# LCD_TFT_40_Pin.net
KiCad netlist of a schematic drawn in Altium Designer
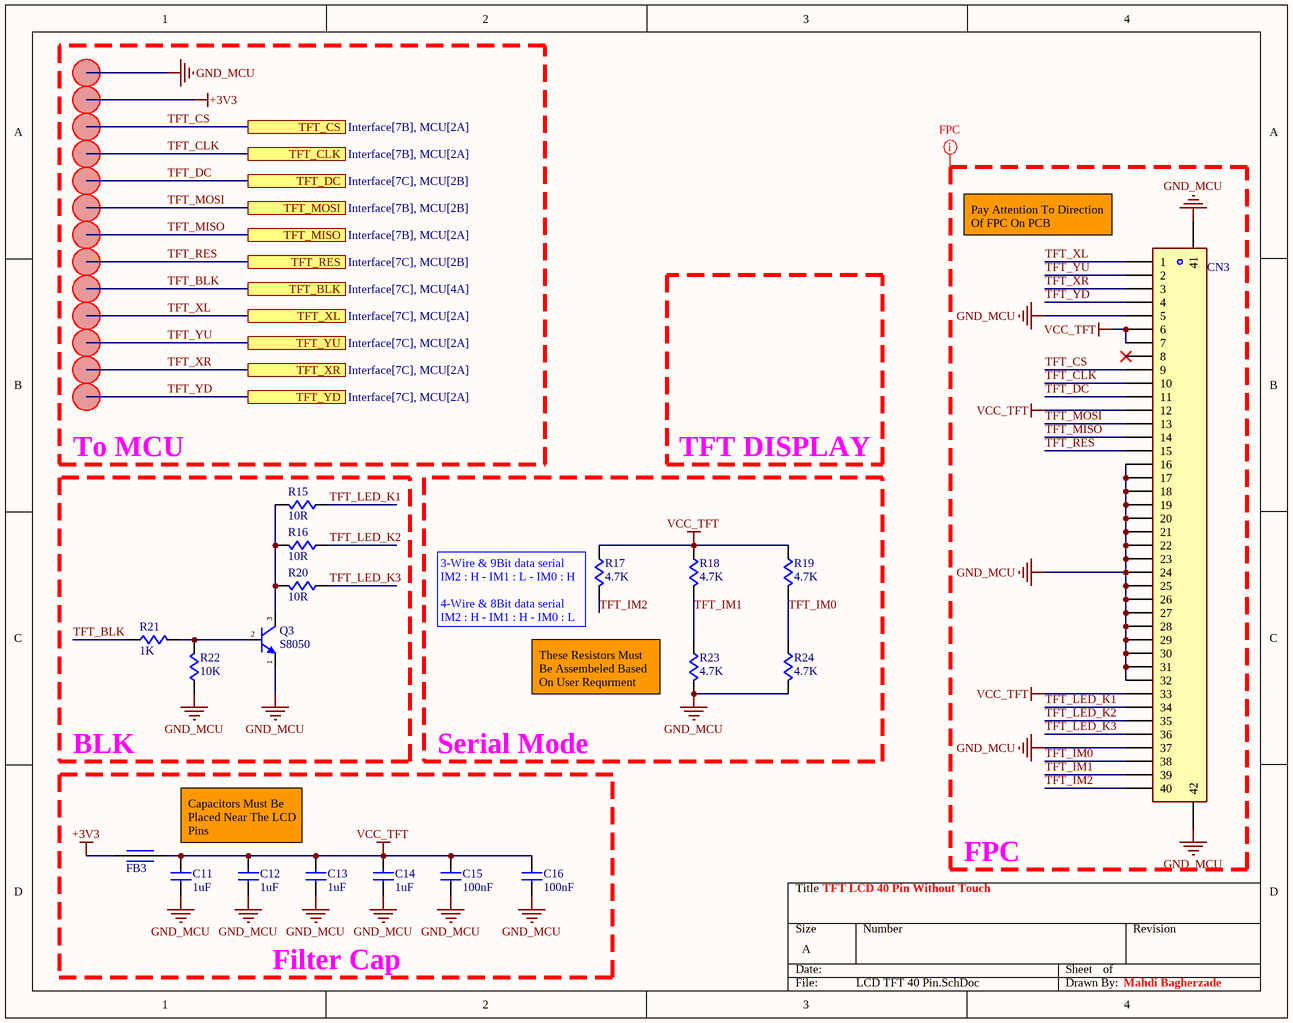
[diagram p0: LCD TFT 40 Pin.SchDoc]

(export (version "E")
  (design (tool "Eeschema 10.0.6"))
  (components
    (comp (ref "C11")
      (value "1uF")
      (footprint "C-0805")
      (description "CAPACITOR")
      (fields
        (field (name "VOLTAGE") "50V")
        (field (name "TOLERANCE") "X7R")
        (field (name "PUBLISHER") "Mahdi Bagherzadeh")
      )
      (libsource (lib "Mahdi-Bagherzadeh") (part "CAP-CER"))
    )
    (comp (ref "C12")
      (value "1uF")
      (footprint "C-0805")
      (description "CAPACITOR")
      (fields
        (field (name "VOLTAGE") "50V")
        (field (name "TOLERANCE") "X7R")
        (field (name "PUBLISHER") "Mahdi Bagherzadeh")
      )
      (libsource (lib "Mahdi-Bagherzadeh") (part "CAP-CER"))
    )
    (comp (ref "C13")
      (value "1uF")
      (footprint "C-0805")
      (description "CAPACITOR")
      (fields
        (field (name "VOLTAGE") "50V")
        (field (name "TOLERANCE") "X7R")
        (field (name "PUBLISHER") "Mahdi Bagherzadeh")
      )
      (libsource (lib "Mahdi-Bagherzadeh") (part "CAP-CER"))
    )
    (comp (ref "C14")
      (value "1uF")
      (footprint "C-0805")
      (description "CAPACITOR")
      (fields
        (field (name "VOLTAGE") "50V")
        (field (name "TOLERANCE") "X7R")
        (field (name "PUBLISHER") "Mahdi Bagherzadeh")
      )
      (libsource (lib "Mahdi-Bagherzadeh") (part "CAP-CER"))
    )
    (comp (ref "C15")
      (value "100nF")
      (footprint "C-0805")
      (description "CAPACITOR")
      (fields
        (field (name "VOLTAGE") "50V")
        (field (name "TOLERANCE") "X7R")
        (field (name "PUBLISHER") "Mahdi Bagherzadeh")
      )
      (libsource (lib "Mahdi-Bagherzadeh") (part "CAP-CER"))
    )
    (comp (ref "C16")
      (value "100nF")
      (footprint "C-0805")
      (description "CAPACITOR")
      (fields
        (field (name "VOLTAGE") "50V")
        (field (name "TOLERANCE") "X7R")
        (field (name "PUBLISHER") "Mahdi Bagherzadeh")
      )
      (libsource (lib "Mahdi-Bagherzadeh") (part "CAP-CER"))
    )
    (comp (ref "CN3")
      (value "Connector FPC Right-2mm-40 Pin")
      (footprint "CN-FPC-40-0.5mm-hor")
      (description "CONNECTOR")
      (fields (field (name "PUBLISHER") "Mahdi Bagherzadeh"))
      (libsource (lib "Mahdi-Bagherzadeh") (part "CN-FPC-40pin"))
    )
    (comp (ref "FB3")
      (value "Ferrite Bead SMD")
      (footprint "FB-0805")
      (description "INDUCATOR")
      (fields (field (name "PUBLISHER") "Mahdi Bagherzadeh"))
      (libsource (lib "Mahdi-Bagherzadeh") (part "FERRITE BEAD"))
    )
    (comp (ref "Q3")
      (value "S8050")
      (footprint "SOT23-213")
      (description "TRANSISTOR")
      (fields (field (name "Comment") "TR S8050-SMD") (field (name "PUBLISHER") "Mahdi Bagherzadeh"))
      (libsource (lib "Mahdi-Bagherzadeh") (part "S8050"))
    )
    (comp (ref "R15")
      (value "10R")
      (footprint "R-0805")
      (description "RESISTOR")
      (fields
        (field (name "POWER") "1/8W")
        (field (name "TOLERANCE") "5%")
        (field (name "PUBLISHER") "Mahdi Bagherzadeh")
      )
      (libsource (lib "Mahdi-Bagherzadeh") (part "RES"))
    )
    (comp (ref "R16")
      (value "10R")
      (footprint "R-0805")
      (description "RESISTOR")
      (fields
        (field (name "POWER") "1/8W")
        (field (name "TOLERANCE") "5%")
        (field (name "PUBLISHER") "Mahdi Bagherzadeh")
      )
      (libsource (lib "Mahdi-Bagherzadeh") (part "RES"))
    )
    (comp (ref "R17")
      (value "4.7K")
      (footprint "R-0805")
      (description "RESISTOR")
      (fields
        (field (name "POWER") "1/8W")
        (field (name "TOLERANCE") "5%")
        (field (name "PUBLISHER") "Mahdi Bagherzadeh")
      )
      (libsource (lib "Mahdi-Bagherzadeh") (part "RES"))
    )
    (comp (ref "R18")
      (value "4.7K")
      (footprint "R-0805")
      (description "RESISTOR")
      (fields
        (field (name "POWER") "1/8W")
        (field (name "TOLERANCE") "5%")
        (field (name "PUBLISHER") "Mahdi Bagherzadeh")
      )
      (libsource (lib "Mahdi-Bagherzadeh") (part "RES"))
    )
    (comp (ref "R19")
      (value "4.7K")
      (footprint "R-0805")
      (description "RESISTOR")
      (fields
        (field (name "POWER") "1/8W")
        (field (name "TOLERANCE") "5%")
        (field (name "PUBLISHER") "Mahdi Bagherzadeh")
      )
      (libsource (lib "Mahdi-Bagherzadeh") (part "RES"))
    )
    (comp (ref "R20")
      (value "10R")
      (footprint "R-0805")
      (description "RESISTOR")
      (fields
        (field (name "POWER") "1/8W")
        (field (name "TOLERANCE") "5%")
        (field (name "PUBLISHER") "Mahdi Bagherzadeh")
      )
      (libsource (lib "Mahdi-Bagherzadeh") (part "RES"))
    )
    (comp (ref "R21")
      (value "1K")
      (footprint "R-0805")
      (description "RESISTOR")
      (fields
        (field (name "POWER") "1/8W")
        (field (name "TOLERANCE") "5%")
        (field (name "PUBLISHER") "Mahdi Bagherzadeh")
      )
      (libsource (lib "Mahdi-Bagherzadeh") (part "RES"))
    )
    (comp (ref "R22")
      (value "10K")
      (footprint "R-0805")
      (description "RESISTOR")
      (fields
        (field (name "POWER") "1/8W")
        (field (name "TOLERANCE") "5%")
        (field (name "PUBLISHER") "Mahdi Bagherzadeh")
      )
      (libsource (lib "Mahdi-Bagherzadeh") (part "RES"))
    )
    (comp (ref "R23")
      (value "4.7K")
      (footprint "R-0805")
      (description "RESISTOR")
      (fields
        (field (name "POWER") "1/8W")
        (field (name "TOLERANCE") "5%")
        (field (name "PUBLISHER") "Mahdi Bagherzadeh")
      )
      (libsource (lib "Mahdi-Bagherzadeh") (part "RES"))
    )
    (comp (ref "R24")
      (value "4.7K")
      (footprint "R-0805")
      (description "RESISTOR")
      (fields
        (field (name "POWER") "1/8W")
        (field (name "TOLERANCE") "5%")
        (field (name "PUBLISHER") "Mahdi Bagherzadeh")
      )
      (libsource (lib "Mahdi-Bagherzadeh") (part "RES"))
    )
    (comp (ref "TP1")
      (value "~")
      (footprint "TEST POINT-DIP")
      (fields (field (name "PUBLISHER") "Mahdi Bagherzadeh"))
      (libsource (lib "Mahdi-Bagherzadeh") (part "TEST PIONT"))
    )
    (comp (ref "TP2")
      (value "~")
      (footprint "TEST POINT-DIP")
      (fields (field (name "PUBLISHER") "Mahdi Bagherzadeh"))
      (libsource (lib "Mahdi-Bagherzadeh") (part "TEST PIONT"))
    )
    (comp (ref "TP3")
      (value "~")
      (footprint "TEST POINT-DIP")
      (fields (field (name "PUBLISHER") "Mahdi Bagherzadeh"))
      (libsource (lib "Mahdi-Bagherzadeh") (part "TEST PIONT"))
    )
    (comp (ref "TP4")
      (value "~")
      (footprint "TEST POINT-DIP")
      (fields (field (name "PUBLISHER") "Mahdi Bagherzadeh"))
      (libsource (lib "Mahdi-Bagherzadeh") (part "TEST PIONT"))
    )
    (comp (ref "TP5")
      (value "~")
      (footprint "TEST POINT-DIP")
      (fields (field (name "PUBLISHER") "Mahdi Bagherzadeh"))
      (libsource (lib "Mahdi-Bagherzadeh") (part "TEST PIONT"))
    )
    (comp (ref "TP6")
      (value "~")
      (footprint "TEST POINT-DIP")
      (fields (field (name "PUBLISHER") "Mahdi Bagherzadeh"))
      (libsource (lib "Mahdi-Bagherzadeh") (part "TEST PIONT"))
    )
    (comp (ref "TP7")
      (value "~")
      (footprint "TEST POINT-DIP")
      (fields (field (name "PUBLISHER") "Mahdi Bagherzadeh"))
      (libsource (lib "Mahdi-Bagherzadeh") (part "TEST PIONT"))
    )
    (comp (ref "TP8")
      (value "~")
      (footprint "TEST POINT-DIP")
      (fields (field (name "PUBLISHER") "Mahdi Bagherzadeh"))
      (libsource (lib "Mahdi-Bagherzadeh") (part "TEST PIONT"))
    )
    (comp (ref "TP9")
      (value "~")
      (footprint "TEST POINT-DIP")
      (fields (field (name "PUBLISHER") "Mahdi Bagherzadeh"))
      (libsource (lib "Mahdi-Bagherzadeh") (part "TEST PIONT"))
    )
    (comp (ref "TP10")
      (value "~")
      (footprint "TEST POINT-DIP")
      (fields (field (name "PUBLISHER") "Mahdi Bagherzadeh"))
      (libsource (lib "Mahdi-Bagherzadeh") (part "TEST PIONT"))
    )
    (comp (ref "TP11")
      (value "~")
      (footprint "TEST POINT-DIP")
      (fields (field (name "PUBLISHER") "Mahdi Bagherzadeh"))
      (libsource (lib "Mahdi-Bagherzadeh") (part "TEST PIONT"))
    )
    (comp (ref "TP12")
      (value "~")
      (footprint "TEST POINT-DIP")
      (fields (field (name "PUBLISHER") "Mahdi Bagherzadeh"))
      (libsource (lib "Mahdi-Bagherzadeh") (part "TEST PIONT"))
    )
    (comp (ref "TP13")
      (value "~")
      (footprint "TEST POINT-DIP")
      (fields (field (name "PUBLISHER") "Mahdi Bagherzadeh"))
      (libsource (lib "Mahdi-Bagherzadeh") (part "TEST PIONT"))
    )
  )
  (nets
    (net (code "1") (name "+3V3") (class "Default")
      (node (ref "FB3") (pin "1") (pinfunction "1_1") (pintype "passive"))
      (node (ref "TP2") (pin "1") (pinfunction "TP_1") (pintype "passive"))
    )
    (net (code "2") (name "/TFT_BLK") (class "Default")
      (node (ref "R21") (pin "1") (pinfunction "1_1") (pintype "passive"))
      (node (ref "TP9") (pin "1") (pinfunction "TP_1") (pintype "passive"))
    )
    (net (code "3") (name "/TFT_CLK") (class "Default")
      (node (ref "CN3") (pin "10") (pinfunction "10_10") (pintype "passive"))
      (node (ref "TP4") (pin "1") (pinfunction "TP_1") (pintype "passive"))
    )
    (net (code "4") (name "/TFT_CS") (class "Default")
      (node (ref "CN3") (pin "9") (pinfunction "9_9") (pintype "passive"))
      (node (ref "TP3") (pin "1") (pinfunction "TP_1") (pintype "passive"))
    )
    (net (code "5") (name "/TFT_DC") (class "Default")
      (node (ref "CN3") (pin "11") (pinfunction "11_11") (pintype "passive"))
      (node (ref "TP5") (pin "1") (pinfunction "TP_1") (pintype "passive"))
    )
    (net (code "6") (name "/TFT_IM0") (class "Default")
      (node (ref "CN3") (pin "38") (pinfunction "38_38") (pintype "passive"))
      (node (ref "R19") (pin "2") (pinfunction "2_2") (pintype "passive"))
      (node (ref "R24") (pin "1") (pinfunction "1_1") (pintype "passive"))
    )
    (net (code "7") (name "/TFT_IM1") (class "Default")
      (node (ref "CN3") (pin "39") (pinfunction "39_39") (pintype "passive"))
      (node (ref "R18") (pin "2") (pinfunction "2_2") (pintype "passive"))
      (node (ref "R23") (pin "1") (pinfunction "1_1") (pintype "passive"))
    )
    (net (code "8") (name "/TFT_IM2") (class "Default")
      (node (ref "CN3") (pin "40") (pinfunction "40_40") (pintype "passive"))
      (node (ref "R17") (pin "2") (pinfunction "2_2") (pintype "passive"))
    )
    (net (code "9") (name "/TFT_LED_K1") (class "Default")
      (node (ref "CN3") (pin "34") (pinfunction "34_34") (pintype "passive"))
      (node (ref "R15") (pin "1") (pinfunction "1_1") (pintype "passive"))
    )
    (net (code "10") (name "/TFT_LED_K2") (class "Default")
      (node (ref "CN3") (pin "35") (pinfunction "35_35") (pintype "passive"))
      (node (ref "R16") (pin "1") (pinfunction "1_1") (pintype "passive"))
    )
    (net (code "11") (name "/TFT_LED_K3") (class "Default")
      (node (ref "CN3") (pin "36") (pinfunction "36_36") (pintype "passive"))
      (node (ref "R20") (pin "1") (pinfunction "1_1") (pintype "passive"))
    )
    (net (code "12") (name "/TFT_MISO") (class "Default")
      (node (ref "CN3") (pin "14") (pinfunction "14_14") (pintype "passive"))
      (node (ref "TP7") (pin "1") (pinfunction "TP_1") (pintype "passive"))
    )
    (net (code "13") (name "/TFT_MOSI") (class "Default")
      (node (ref "CN3") (pin "13") (pinfunction "13_13") (pintype "passive"))
      (node (ref "TP6") (pin "1") (pinfunction "TP_1") (pintype "passive"))
    )
    (net (code "14") (name "/TFT_RES") (class "Default")
      (node (ref "CN3") (pin "15") (pinfunction "15_15") (pintype "passive"))
      (node (ref "TP8") (pin "1") (pinfunction "TP_1") (pintype "passive"))
    )
    (net (code "15") (name "/TFT_XL") (class "Default")
      (node (ref "CN3") (pin "1") (pinfunction "1_1") (pintype "passive"))
      (node (ref "TP10") (pin "1") (pinfunction "TP_1") (pintype "passive"))
    )
    (net (code "16") (name "/TFT_XR") (class "Default")
      (node (ref "CN3") (pin "3") (pinfunction "3_3") (pintype "passive"))
      (node (ref "TP12") (pin "1") (pinfunction "TP_1") (pintype "passive"))
    )
    (net (code "17") (name "/TFT_YD") (class "Default")
      (node (ref "CN3") (pin "4") (pinfunction "4_4") (pintype "passive"))
      (node (ref "TP13") (pin "1") (pinfunction "TP_1") (pintype "passive"))
    )
    (net (code "18") (name "/TFT_YU") (class "Default")
      (node (ref "CN3") (pin "2") (pinfunction "2_2") (pintype "passive"))
      (node (ref "TP11") (pin "1") (pinfunction "TP_1") (pintype "passive"))
    )
    (net (code "19") (name "GND_MCU") (class "Default")
      (node (ref "C11") (pin "1") (pinfunction "1_1") (pintype "passive"))
      (node (ref "C12") (pin "1") (pinfunction "1_1") (pintype "passive"))
      (node (ref "C13") (pin "1") (pinfunction "1_1") (pintype "passive"))
      (node (ref "C14") (pin "1") (pinfunction "1_1") (pintype "passive"))
      (node (ref "C15") (pin "1") (pinfunction "1_1") (pintype "passive"))
      (node (ref "C16") (pin "1") (pinfunction "1_1") (pintype "passive"))
      (node (ref "CN3") (pin "16") (pinfunction "16_16") (pintype "passive"))
      (node (ref "CN3") (pin "17") (pinfunction "17_17") (pintype "passive"))
      (node (ref "CN3") (pin "18") (pinfunction "18_18") (pintype "passive"))
      (node (ref "CN3") (pin "19") (pinfunction "19_19") (pintype "passive"))
      (node (ref "CN3") (pin "20") (pinfunction "20_20") (pintype "passive"))
      (node (ref "CN3") (pin "21") (pinfunction "21_21") (pintype "passive"))
      (node (ref "CN3") (pin "22") (pinfunction "22_22") (pintype "passive"))
      (node (ref "CN3") (pin "23") (pinfunction "23_23") (pintype "passive"))
      (node (ref "CN3") (pin "24") (pinfunction "24_24") (pintype "passive"))
      (node (ref "CN3") (pin "25") (pinfunction "25_25") (pintype "passive"))
      (node (ref "CN3") (pin "26") (pinfunction "26_26") (pintype "passive"))
      (node (ref "CN3") (pin "27") (pinfunction "27_27") (pintype "passive"))
      (node (ref "CN3") (pin "28") (pinfunction "28_28") (pintype "passive"))
      (node (ref "CN3") (pin "29") (pinfunction "29_29") (pintype "passive"))
      (node (ref "CN3") (pin "30") (pinfunction "30_30") (pintype "passive"))
      (node (ref "CN3") (pin "31") (pinfunction "31_31") (pintype "passive"))
      (node (ref "CN3") (pin "32") (pinfunction "32_32") (pintype "passive"))
      (node (ref "CN3") (pin "37") (pinfunction "37_37") (pintype "passive"))
      (node (ref "CN3") (pin "41") (pinfunction "41_41") (pintype "passive"))
      (node (ref "CN3") (pin "42") (pinfunction "42_42") (pintype "passive"))
      (node (ref "CN3") (pin "5") (pinfunction "5_5") (pintype "passive"))
      (node (ref "Q3") (pin "1") (pinfunction "E_1") (pintype "passive"))
      (node (ref "R22") (pin "1") (pinfunction "1_1") (pintype "passive"))
      (node (ref "R23") (pin "2") (pinfunction "2_2") (pintype "passive"))
      (node (ref "R24") (pin "2") (pinfunction "2_2") (pintype "passive"))
      (node (ref "TP1") (pin "1") (pinfunction "TP_1") (pintype "passive"))
    )
    (net (code "20") (name "Net-(Q3-B)") (class "Default")
      (node (ref "Q3") (pin "2") (pinfunction "B_2") (pintype "passive"))
      (node (ref "R21") (pin "2") (pinfunction "2_2") (pintype "passive"))
      (node (ref "R22") (pin "2") (pinfunction "2_2") (pintype "passive"))
    )
    (net (code "21") (name "Net-(Q3-C)") (class "Default")
      (node (ref "Q3") (pin "3") (pinfunction "C_3") (pintype "passive"))
      (node (ref "R15") (pin "2") (pinfunction "2_2") (pintype "passive"))
      (node (ref "R16") (pin "2") (pinfunction "2_2") (pintype "passive"))
      (node (ref "R20") (pin "2") (pinfunction "2_2") (pintype "passive"))
    )
    (net (code "22") (name "VCC_TFT") (class "Default")
      (node (ref "C11") (pin "2") (pinfunction "2_2") (pintype "passive"))
      (node (ref "C12") (pin "2") (pinfunction "2_2") (pintype "passive"))
      (node (ref "C13") (pin "2") (pinfunction "2_2") (pintype "passive"))
      (node (ref "C14") (pin "2") (pinfunction "2_2") (pintype "passive"))
      (node (ref "C15") (pin "2") (pinfunction "2_2") (pintype "passive"))
      (node (ref "C16") (pin "2") (pinfunction "2_2") (pintype "passive"))
      (node (ref "CN3") (pin "12") (pinfunction "12_12") (pintype "passive"))
      (node (ref "CN3") (pin "33") (pinfunction "33_33") (pintype "passive"))
      (node (ref "CN3") (pin "6") (pinfunction "6_6") (pintype "passive"))
      (node (ref "CN3") (pin "7") (pinfunction "7_7") (pintype "passive"))
      (node (ref "FB3") (pin "2") (pinfunction "2_2") (pintype "passive"))
      (node (ref "R17") (pin "1") (pinfunction "1_1") (pintype "passive"))
      (node (ref "R18") (pin "1") (pinfunction "1_1") (pintype "passive"))
      (node (ref "R19") (pin "1") (pinfunction "1_1") (pintype "passive"))
    )
    (net (code "23") (name "unconnected-(CN3-Pad8)") (class "Default")
      (node (ref "CN3") (pin "8") (pinfunction "8_8") (pintype "passive+no_connect"))
    )
  )
)
